# PLCC-20-breakout.net
KiCad netlist of a schematic drawn in EAGLE
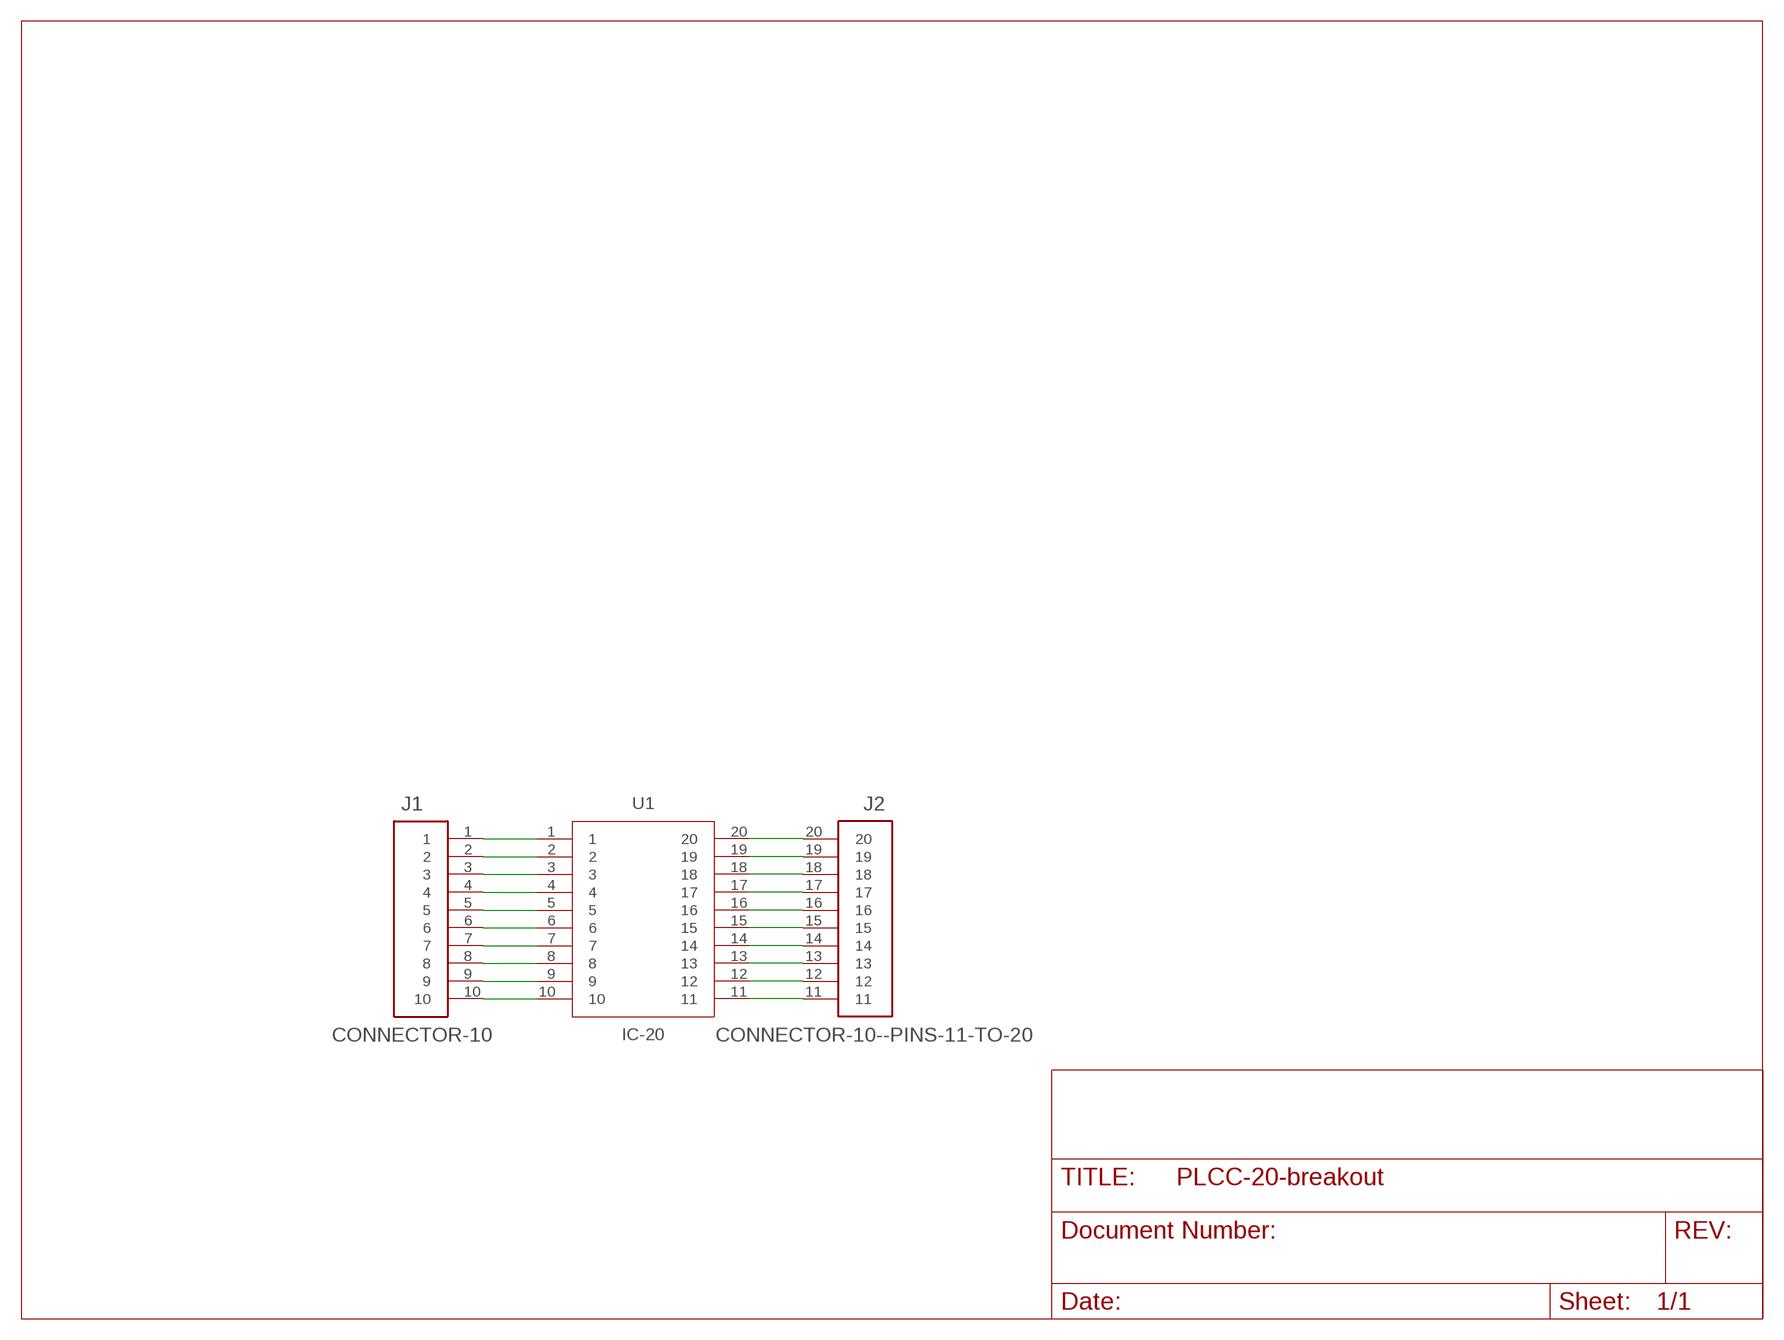
[diagram p0: schematic, sheet 1]

(export (version "E")
  (design (tool "Eeschema 10.0.6"))
  (components
    (comp (ref "J1")
      (value "CONNECTOR-10")
      (footprint "eagle-import:ESQ-110-XX-XX-S")
      (libsource (lib "eagle-import") (part "CONNECTOR-10"))
    )
    (comp (ref "J2")
      (value "CONNECTOR-10--PINS-11-TO-20")
      (footprint "eagle-import:ESQ-110-XX-XX-S--ROUND-PIN-1")
      (libsource (lib "eagle-import") (part "CONNECTOR-10--PINS-11-TO-20"))
    )
    (comp (ref "U1")
      (value "IC-20")
      (footprint "eagle-import:PLCC127P990X990X457-20N")
      (libsource (lib "eagle-import") (part "IC-20"))
    )
  )
  (nets
    (net (code "1") (name "Net-(J1-Pad1)") (class "Default")
      (node (ref "J1") (pin "1") (pinfunction "1_1") (pintype "bidirectional"))
      (node (ref "U1") (pin "1") (pinfunction "1_1") (pintype "bidirectional"))
    )
    (net (code "2") (name "Net-(J1-Pad2)") (class "Default")
      (node (ref "J1") (pin "2") (pinfunction "2_2") (pintype "bidirectional"))
      (node (ref "U1") (pin "2") (pinfunction "2_2") (pintype "bidirectional"))
    )
    (net (code "3") (name "Net-(J1-Pad3)") (class "Default")
      (node (ref "J1") (pin "3") (pinfunction "3_3") (pintype "bidirectional"))
      (node (ref "U1") (pin "3") (pinfunction "3_3") (pintype "bidirectional"))
    )
    (net (code "4") (name "Net-(J1-Pad4)") (class "Default")
      (node (ref "J1") (pin "4") (pinfunction "4_4") (pintype "bidirectional"))
      (node (ref "U1") (pin "4") (pinfunction "4_4") (pintype "bidirectional"))
    )
    (net (code "5") (name "Net-(J1-Pad5)") (class "Default")
      (node (ref "J1") (pin "5") (pinfunction "5_5") (pintype "bidirectional"))
      (node (ref "U1") (pin "5") (pinfunction "5_5") (pintype "bidirectional"))
    )
    (net (code "6") (name "Net-(J1-Pad6)") (class "Default")
      (node (ref "J1") (pin "6") (pinfunction "6_6") (pintype "bidirectional"))
      (node (ref "U1") (pin "6") (pinfunction "6_6") (pintype "bidirectional"))
    )
    (net (code "7") (name "Net-(J1-Pad7)") (class "Default")
      (node (ref "J1") (pin "7") (pinfunction "7_7") (pintype "bidirectional"))
      (node (ref "U1") (pin "7") (pinfunction "7_7") (pintype "bidirectional"))
    )
    (net (code "8") (name "Net-(J1-Pad8)") (class "Default")
      (node (ref "J1") (pin "8") (pinfunction "8_8") (pintype "bidirectional"))
      (node (ref "U1") (pin "8") (pinfunction "8_8") (pintype "bidirectional"))
    )
    (net (code "9") (name "Net-(J1-Pad9)") (class "Default")
      (node (ref "J1") (pin "9") (pinfunction "9_9") (pintype "bidirectional"))
      (node (ref "U1") (pin "9") (pinfunction "9_9") (pintype "bidirectional"))
    )
    (net (code "10") (name "Net-(J1-Pad10)") (class "Default")
      (node (ref "J1") (pin "10") (pinfunction "10_10") (pintype "bidirectional"))
      (node (ref "U1") (pin "10") (pinfunction "10_10") (pintype "bidirectional"))
    )
    (net (code "11") (name "Net-(J2-Pad11)") (class "Default")
      (node (ref "J2") (pin "11") (pinfunction "11_11") (pintype "bidirectional"))
      (node (ref "U1") (pin "11") (pinfunction "11_11") (pintype "bidirectional"))
    )
    (net (code "12") (name "Net-(J2-Pad12)") (class "Default")
      (node (ref "J2") (pin "12") (pinfunction "12_12") (pintype "bidirectional"))
      (node (ref "U1") (pin "12") (pinfunction "12_12") (pintype "bidirectional"))
    )
    (net (code "13") (name "Net-(J2-Pad13)") (class "Default")
      (node (ref "J2") (pin "13") (pinfunction "13_13") (pintype "bidirectional"))
      (node (ref "U1") (pin "13") (pinfunction "13_13") (pintype "bidirectional"))
    )
    (net (code "14") (name "Net-(J2-Pad14)") (class "Default")
      (node (ref "J2") (pin "14") (pinfunction "14_14") (pintype "bidirectional"))
      (node (ref "U1") (pin "14") (pinfunction "14_14") (pintype "bidirectional"))
    )
    (net (code "15") (name "Net-(J2-Pad15)") (class "Default")
      (node (ref "J2") (pin "15") (pinfunction "15_15") (pintype "bidirectional"))
      (node (ref "U1") (pin "15") (pinfunction "15_15") (pintype "bidirectional"))
    )
    (net (code "16") (name "Net-(J2-Pad16)") (class "Default")
      (node (ref "J2") (pin "16") (pinfunction "16_16") (pintype "bidirectional"))
      (node (ref "U1") (pin "16") (pinfunction "16_16") (pintype "bidirectional"))
    )
    (net (code "17") (name "Net-(J2-Pad17)") (class "Default")
      (node (ref "J2") (pin "17") (pinfunction "17_17") (pintype "bidirectional"))
      (node (ref "U1") (pin "17") (pinfunction "17_17") (pintype "bidirectional"))
    )
    (net (code "18") (name "Net-(J2-Pad18)") (class "Default")
      (node (ref "J2") (pin "18") (pinfunction "18_18") (pintype "bidirectional"))
      (node (ref "U1") (pin "18") (pinfunction "18_18") (pintype "bidirectional"))
    )
    (net (code "19") (name "Net-(J2-Pad19)") (class "Default")
      (node (ref "J2") (pin "19") (pinfunction "19_19") (pintype "bidirectional"))
      (node (ref "U1") (pin "19") (pinfunction "19_19") (pintype "bidirectional"))
    )
    (net (code "20") (name "Net-(J2-Pad20)") (class "Default")
      (node (ref "J2") (pin "20") (pinfunction "20_20") (pintype "bidirectional"))
      (node (ref "U1") (pin "20") (pinfunction "20_20") (pintype "bidirectional"))
    )
  )
)
